# takas.net
KiCad netlist of a schematic drawn in Altium Designer
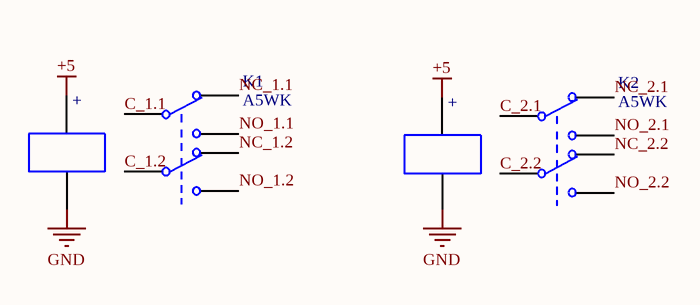
[diagram p0: takas.SchDoc]

(export (version "E")
  (design (tool "Eeschema 10.0.6"))
  (components
    (comp (ref "K1")
      (value "ReleDPDT")
      (footprint "A5WK")
      (description "Electromecánicos Relés  [A5WK / Fujitsu]")
      (fields (field (name "MODELO") "A5WK"))
      (libsource (lib "ComponentesHomologados") (part "ReleDPDT"))
    )
    (comp (ref "K2")
      (value "ReleDPDT")
      (footprint "A5WK")
      (description "Electromecánicos Relés  [A5WK / Fujitsu]")
      (fields (field (name "MODELO") "A5WK"))
      (libsource (lib "ComponentesHomologados") (part "ReleDPDT"))
    )
  )
  (nets
    (net (code "1") (name "+5") (class "Default")
      (node (ref "K1") (pin "1") (pinfunction "1_1") (pintype "passive"))
      (node (ref "K2") (pin "1") (pinfunction "1_1") (pintype "passive"))
    )
    (net (code "2") (name "/C_1.1") (class "Default")
      (node (ref "K1") (pin "9") (pinfunction "9_9") (pintype "passive"))
    )
    (net (code "3") (name "/C_1.2") (class "Default")
      (node (ref "K1") (pin "3") (pinfunction "3_3") (pintype "passive"))
    )
    (net (code "4") (name "/C_2.1") (class "Default")
      (node (ref "K2") (pin "9") (pinfunction "9_9") (pintype "passive"))
    )
    (net (code "5") (name "/C_2.2") (class "Default")
      (node (ref "K2") (pin "3") (pinfunction "3_3") (pintype "passive"))
    )
    (net (code "6") (name "/NC_1.1") (class "Default")
      (node (ref "K1") (pin "10") (pinfunction "10_10") (pintype "passive"))
    )
    (net (code "7") (name "/NC_1.2") (class "Default")
      (node (ref "K1") (pin "2") (pinfunction "2_2") (pintype "passive"))
    )
    (net (code "8") (name "/NC_2.1") (class "Default")
      (node (ref "K2") (pin "10") (pinfunction "10_10") (pintype "passive"))
    )
    (net (code "9") (name "/NC_2.2") (class "Default")
      (node (ref "K2") (pin "2") (pinfunction "2_2") (pintype "passive"))
    )
    (net (code "10") (name "/NO_1.1") (class "Default")
      (node (ref "K1") (pin "8") (pinfunction "8_8") (pintype "passive"))
    )
    (net (code "11") (name "/NO_1.2") (class "Default")
      (node (ref "K1") (pin "4") (pinfunction "4_4") (pintype "passive"))
    )
    (net (code "12") (name "/NO_2.1") (class "Default")
      (node (ref "K2") (pin "8") (pinfunction "8_8") (pintype "passive"))
    )
    (net (code "13") (name "/NO_2.2") (class "Default")
      (node (ref "K2") (pin "4") (pinfunction "4_4") (pintype "passive"))
    )
    (net (code "14") (name "GND") (class "Default")
      (node (ref "K1") (pin "12") (pinfunction "12_12") (pintype "passive"))
    )
    (net (code "15") (name "unconnected-(K2-Pad12)") (class "Default")
      (node (ref "K2") (pin "12") (pinfunction "12_12") (pintype "passive"))
    )
  )
)
